# EagleVersion1_PowerPatch.net
KiCad netlist of a schematic drawn in EAGLE
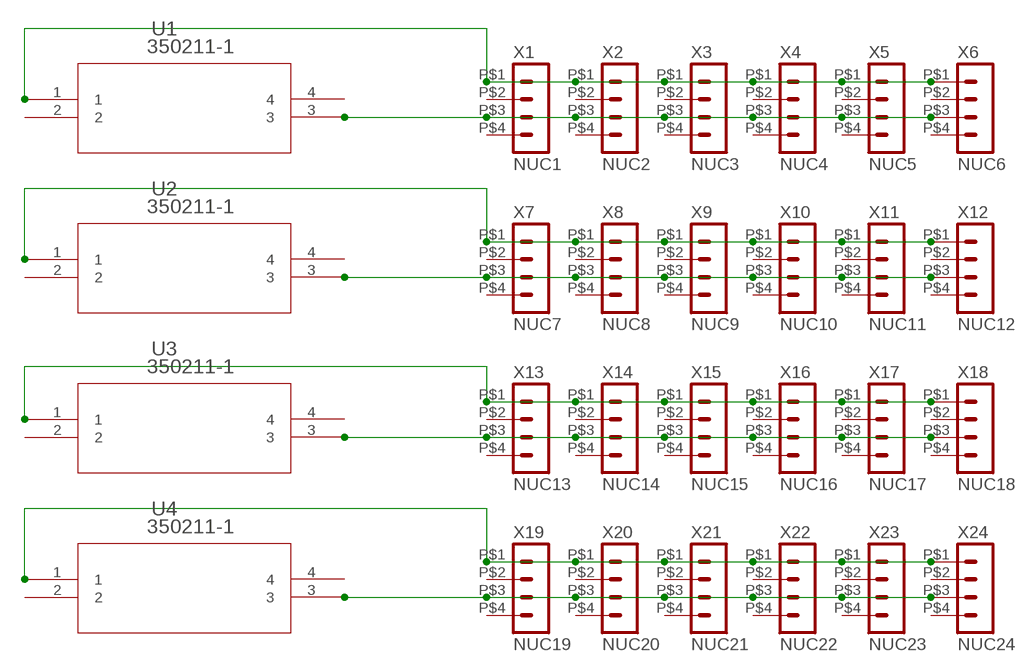
[diagram p0: schematic, sheet 1]

(export (version "E")
  (design (tool "Eeschema 10.0.6"))
  (components
    (comp (ref "U1")
      (value "350211-1")
      (footprint "eagle-import:350211-1")
      (fields
        (field (name "MANUFACTURER_PART_NUMBER") "3502111")
        (field (name "COPYRIGHT") "Copyright C 2015 Accelerated Designs. All rights reserved")
      )
      (libsource (lib "eagle-import") (part "350211-1"))
    )
    (comp (ref "U2")
      (value "350211-1")
      (footprint "eagle-import:350211-1")
      (fields
        (field (name "MANUFACTURER_PART_NUMBER") "3502111")
        (field (name "COPYRIGHT") "Copyright C 2015 Accelerated Designs. All rights reserved")
      )
      (libsource (lib "eagle-import") (part "350211-1"))
    )
    (comp (ref "U3")
      (value "350211-1")
      (footprint "eagle-import:350211-1")
      (fields
        (field (name "MANUFACTURER_PART_NUMBER") "3502111")
        (field (name "COPYRIGHT") "Copyright C 2015 Accelerated Designs. All rights reserved")
      )
      (libsource (lib "eagle-import") (part "350211-1"))
    )
    (comp (ref "U4")
      (value "350211-1")
      (footprint "eagle-import:350211-1")
      (fields
        (field (name "MANUFACTURER_PART_NUMBER") "3502111")
        (field (name "COPYRIGHT") "Copyright C 2015 Accelerated Designs. All rights reserved")
      )
      (libsource (lib "eagle-import") (part "350211-1"))
    )
    (comp (ref "X1")
      (value "NUC1")
      (footprint "eagle-import:43045-0412")
      (libsource (lib "eagle-import") (part "HEADER_POS4_?43045-0412"))
    )
    (comp (ref "X2")
      (value "NUC2")
      (footprint "eagle-import:43045-0412")
      (libsource (lib "eagle-import") (part "HEADER_POS4_?43045-0412"))
    )
    (comp (ref "X3")
      (value "NUC3")
      (footprint "eagle-import:43045-0412")
      (libsource (lib "eagle-import") (part "HEADER_POS4_?43045-0412"))
    )
    (comp (ref "X4")
      (value "NUC4")
      (footprint "eagle-import:43045-0412")
      (libsource (lib "eagle-import") (part "HEADER_POS4_?43045-0412"))
    )
    (comp (ref "X5")
      (value "NUC5")
      (footprint "eagle-import:43045-0412")
      (libsource (lib "eagle-import") (part "HEADER_POS4_?43045-0412"))
    )
    (comp (ref "X6")
      (value "NUC6")
      (footprint "eagle-import:43045-0412")
      (libsource (lib "eagle-import") (part "HEADER_POS4_?43045-0412"))
    )
    (comp (ref "X7")
      (value "NUC7")
      (footprint "eagle-import:43045-0412")
      (libsource (lib "eagle-import") (part "HEADER_POS4_?43045-0412"))
    )
    (comp (ref "X8")
      (value "NUC8")
      (footprint "eagle-import:43045-0412")
      (libsource (lib "eagle-import") (part "HEADER_POS4_?43045-0412"))
    )
    (comp (ref "X9")
      (value "NUC9")
      (footprint "eagle-import:43045-0412")
      (libsource (lib "eagle-import") (part "HEADER_POS4_?43045-0412"))
    )
    (comp (ref "X10")
      (value "NUC10")
      (footprint "eagle-import:43045-0412")
      (libsource (lib "eagle-import") (part "HEADER_POS4_?43045-0412"))
    )
    (comp (ref "X11")
      (value "NUC11")
      (footprint "eagle-import:43045-0412")
      (libsource (lib "eagle-import") (part "HEADER_POS4_?43045-0412"))
    )
    (comp (ref "X12")
      (value "NUC12")
      (footprint "eagle-import:43045-0412")
      (libsource (lib "eagle-import") (part "HEADER_POS4_?43045-0412"))
    )
    (comp (ref "X13")
      (value "NUC13")
      (footprint "eagle-import:43045-0412")
      (libsource (lib "eagle-import") (part "HEADER_POS4_?43045-0412"))
    )
    (comp (ref "X14")
      (value "NUC14")
      (footprint "eagle-import:43045-0412")
      (libsource (lib "eagle-import") (part "HEADER_POS4_?43045-0412"))
    )
    (comp (ref "X15")
      (value "NUC15")
      (footprint "eagle-import:43045-0412")
      (libsource (lib "eagle-import") (part "HEADER_POS4_?43045-0412"))
    )
    (comp (ref "X16")
      (value "NUC16")
      (footprint "eagle-import:43045-0412")
      (libsource (lib "eagle-import") (part "HEADER_POS4_?43045-0412"))
    )
    (comp (ref "X17")
      (value "NUC17")
      (footprint "eagle-import:43045-0412")
      (libsource (lib "eagle-import") (part "HEADER_POS4_?43045-0412"))
    )
    (comp (ref "X18")
      (value "NUC18")
      (footprint "eagle-import:43045-0412")
      (libsource (lib "eagle-import") (part "HEADER_POS4_?43045-0412"))
    )
    (comp (ref "X19")
      (value "NUC19")
      (footprint "eagle-import:43045-0412")
      (libsource (lib "eagle-import") (part "HEADER_POS4_?43045-0412"))
    )
    (comp (ref "X20")
      (value "NUC20")
      (footprint "eagle-import:43045-0412")
      (libsource (lib "eagle-import") (part "HEADER_POS4_?43045-0412"))
    )
    (comp (ref "X21")
      (value "NUC21")
      (footprint "eagle-import:43045-0412")
      (libsource (lib "eagle-import") (part "HEADER_POS4_?43045-0412"))
    )
    (comp (ref "X22")
      (value "NUC22")
      (footprint "eagle-import:43045-0412")
      (libsource (lib "eagle-import") (part "HEADER_POS4_?43045-0412"))
    )
    (comp (ref "X23")
      (value "NUC23")
      (footprint "eagle-import:43045-0412")
      (libsource (lib "eagle-import") (part "HEADER_POS4_?43045-0412"))
    )
    (comp (ref "X24")
      (value "NUC24")
      (footprint "eagle-import:43045-0412")
      (libsource (lib "eagle-import") (part "HEADER_POS4_?43045-0412"))
    )
  )
  (nets
    (net (code "1") (name "Net-(X1-1)") (class "Default")
      (node (ref "U1") (pin "1") (pinfunction "1_1") (pintype "passive"))
      (node (ref "X1") (pin "P$1") (pinfunction "1_P$1") (pintype "passive"))
      (node (ref "X2") (pin "P$1") (pinfunction "1_P$1") (pintype "passive"))
      (node (ref "X3") (pin "P$1") (pinfunction "1_P$1") (pintype "passive"))
      (node (ref "X4") (pin "P$1") (pinfunction "1_P$1") (pintype "passive"))
      (node (ref "X5") (pin "P$1") (pinfunction "1_P$1") (pintype "passive"))
      (node (ref "X6") (pin "P$1") (pinfunction "1_P$1") (pintype "passive"))
    )
    (net (code "2") (name "Net-(X1-3)") (class "Default")
      (node (ref "U1") (pin "3") (pinfunction "3_3") (pintype "passive"))
      (node (ref "X1") (pin "P$3") (pinfunction "3_P$3") (pintype "passive"))
      (node (ref "X2") (pin "P$3") (pinfunction "3_P$3") (pintype "passive"))
      (node (ref "X3") (pin "P$3") (pinfunction "3_P$3") (pintype "passive"))
      (node (ref "X4") (pin "P$3") (pinfunction "3_P$3") (pintype "passive"))
      (node (ref "X5") (pin "P$3") (pinfunction "3_P$3") (pintype "passive"))
      (node (ref "X6") (pin "P$3") (pinfunction "3_P$3") (pintype "passive"))
    )
    (net (code "3") (name "Net-(X10-1)") (class "Default")
      (node (ref "U2") (pin "1") (pinfunction "1_1") (pintype "passive"))
      (node (ref "X10") (pin "P$1") (pinfunction "1_P$1") (pintype "passive"))
      (node (ref "X11") (pin "P$1") (pinfunction "1_P$1") (pintype "passive"))
      (node (ref "X12") (pin "P$1") (pinfunction "1_P$1") (pintype "passive"))
      (node (ref "X7") (pin "P$1") (pinfunction "1_P$1") (pintype "passive"))
      (node (ref "X8") (pin "P$1") (pinfunction "1_P$1") (pintype "passive"))
      (node (ref "X9") (pin "P$1") (pinfunction "1_P$1") (pintype "passive"))
    )
    (net (code "4") (name "Net-(X10-3)") (class "Default")
      (node (ref "U2") (pin "3") (pinfunction "3_3") (pintype "passive"))
      (node (ref "X10") (pin "P$3") (pinfunction "3_P$3") (pintype "passive"))
      (node (ref "X11") (pin "P$3") (pinfunction "3_P$3") (pintype "passive"))
      (node (ref "X12") (pin "P$3") (pinfunction "3_P$3") (pintype "passive"))
      (node (ref "X7") (pin "P$3") (pinfunction "3_P$3") (pintype "passive"))
      (node (ref "X8") (pin "P$3") (pinfunction "3_P$3") (pintype "passive"))
      (node (ref "X9") (pin "P$3") (pinfunction "3_P$3") (pintype "passive"))
    )
    (net (code "5") (name "Net-(X13-1)") (class "Default")
      (node (ref "U3") (pin "1") (pinfunction "1_1") (pintype "passive"))
      (node (ref "X13") (pin "P$1") (pinfunction "1_P$1") (pintype "passive"))
      (node (ref "X14") (pin "P$1") (pinfunction "1_P$1") (pintype "passive"))
      (node (ref "X15") (pin "P$1") (pinfunction "1_P$1") (pintype "passive"))
      (node (ref "X16") (pin "P$1") (pinfunction "1_P$1") (pintype "passive"))
      (node (ref "X17") (pin "P$1") (pinfunction "1_P$1") (pintype "passive"))
      (node (ref "X18") (pin "P$1") (pinfunction "1_P$1") (pintype "passive"))
    )
    (net (code "6") (name "Net-(X13-3)") (class "Default")
      (node (ref "U3") (pin "3") (pinfunction "3_3") (pintype "passive"))
      (node (ref "X13") (pin "P$3") (pinfunction "3_P$3") (pintype "passive"))
      (node (ref "X14") (pin "P$3") (pinfunction "3_P$3") (pintype "passive"))
      (node (ref "X15") (pin "P$3") (pinfunction "3_P$3") (pintype "passive"))
      (node (ref "X16") (pin "P$3") (pinfunction "3_P$3") (pintype "passive"))
      (node (ref "X17") (pin "P$3") (pinfunction "3_P$3") (pintype "passive"))
      (node (ref "X18") (pin "P$3") (pinfunction "3_P$3") (pintype "passive"))
    )
    (net (code "7") (name "Net-(X19-1)") (class "Default")
      (node (ref "U4") (pin "1") (pinfunction "1_1") (pintype "passive"))
      (node (ref "X19") (pin "P$1") (pinfunction "1_P$1") (pintype "passive"))
      (node (ref "X20") (pin "P$1") (pinfunction "1_P$1") (pintype "passive"))
      (node (ref "X21") (pin "P$1") (pinfunction "1_P$1") (pintype "passive"))
      (node (ref "X22") (pin "P$1") (pinfunction "1_P$1") (pintype "passive"))
      (node (ref "X23") (pin "P$1") (pinfunction "1_P$1") (pintype "passive"))
      (node (ref "X24") (pin "P$1") (pinfunction "1_P$1") (pintype "passive"))
    )
    (net (code "8") (name "Net-(X19-3)") (class "Default")
      (node (ref "U4") (pin "3") (pinfunction "3_3") (pintype "passive"))
      (node (ref "X19") (pin "P$3") (pinfunction "3_P$3") (pintype "passive"))
      (node (ref "X20") (pin "P$3") (pinfunction "3_P$3") (pintype "passive"))
      (node (ref "X21") (pin "P$3") (pinfunction "3_P$3") (pintype "passive"))
      (node (ref "X22") (pin "P$3") (pinfunction "3_P$3") (pintype "passive"))
      (node (ref "X23") (pin "P$3") (pinfunction "3_P$3") (pintype "passive"))
      (node (ref "X24") (pin "P$3") (pinfunction "3_P$3") (pintype "passive"))
    )
    (net (code "9") (name "unconnected-(U1-Pad2)") (class "Default")
      (node (ref "U1") (pin "2") (pinfunction "2_2") (pintype "passive"))
    )
    (net (code "10") (name "unconnected-(U1-Pad4)") (class "Default")
      (node (ref "U1") (pin "4") (pinfunction "4_4") (pintype "passive"))
    )
    (net (code "11") (name "unconnected-(U2-Pad2)") (class "Default")
      (node (ref "U2") (pin "2") (pinfunction "2_2") (pintype "passive"))
    )
    (net (code "12") (name "unconnected-(U2-Pad4)") (class "Default")
      (node (ref "U2") (pin "4") (pinfunction "4_4") (pintype "passive"))
    )
    (net (code "13") (name "unconnected-(U3-Pad2)") (class "Default")
      (node (ref "U3") (pin "2") (pinfunction "2_2") (pintype "passive"))
    )
    (net (code "14") (name "unconnected-(U3-Pad4)") (class "Default")
      (node (ref "U3") (pin "4") (pinfunction "4_4") (pintype "passive"))
    )
    (net (code "15") (name "unconnected-(U4-Pad2)") (class "Default")
      (node (ref "U4") (pin "2") (pinfunction "2_2") (pintype "passive"))
    )
    (net (code "16") (name "unconnected-(U4-Pad4)") (class "Default")
      (node (ref "U4") (pin "4") (pinfunction "4_4") (pintype "passive"))
    )
    (net (code "17") (name "unconnected-(X1-2-PadP$2)") (class "Default")
      (node (ref "X1") (pin "P$2") (pinfunction "2_P$2") (pintype "passive"))
    )
    (net (code "18") (name "unconnected-(X1-4-PadP$4)") (class "Default")
      (node (ref "X1") (pin "P$4") (pinfunction "4_P$4") (pintype "passive"))
    )
    (net (code "19") (name "unconnected-(X2-2-PadP$2)") (class "Default")
      (node (ref "X2") (pin "P$2") (pinfunction "2_P$2") (pintype "passive"))
    )
    (net (code "20") (name "unconnected-(X2-4-PadP$4)") (class "Default")
      (node (ref "X2") (pin "P$4") (pinfunction "4_P$4") (pintype "passive"))
    )
    (net (code "21") (name "unconnected-(X3-2-PadP$2)") (class "Default")
      (node (ref "X3") (pin "P$2") (pinfunction "2_P$2") (pintype "passive"))
    )
    (net (code "22") (name "unconnected-(X3-4-PadP$4)") (class "Default")
      (node (ref "X3") (pin "P$4") (pinfunction "4_P$4") (pintype "passive"))
    )
    (net (code "23") (name "unconnected-(X4-2-PadP$2)") (class "Default")
      (node (ref "X4") (pin "P$2") (pinfunction "2_P$2") (pintype "passive"))
    )
    (net (code "24") (name "unconnected-(X4-4-PadP$4)") (class "Default")
      (node (ref "X4") (pin "P$4") (pinfunction "4_P$4") (pintype "passive"))
    )
    (net (code "25") (name "unconnected-(X5-2-PadP$2)") (class "Default")
      (node (ref "X5") (pin "P$2") (pinfunction "2_P$2") (pintype "passive"))
    )
    (net (code "26") (name "unconnected-(X5-4-PadP$4)") (class "Default")
      (node (ref "X5") (pin "P$4") (pinfunction "4_P$4") (pintype "passive"))
    )
    (net (code "27") (name "unconnected-(X6-2-PadP$2)") (class "Default")
      (node (ref "X6") (pin "P$2") (pinfunction "2_P$2") (pintype "passive"))
    )
    (net (code "28") (name "unconnected-(X6-4-PadP$4)") (class "Default")
      (node (ref "X6") (pin "P$4") (pinfunction "4_P$4") (pintype "passive"))
    )
    (net (code "29") (name "unconnected-(X7-2-PadP$2)") (class "Default")
      (node (ref "X7") (pin "P$2") (pinfunction "2_P$2") (pintype "passive"))
    )
    (net (code "30") (name "unconnected-(X7-4-PadP$4)") (class "Default")
      (node (ref "X7") (pin "P$4") (pinfunction "4_P$4") (pintype "passive"))
    )
    (net (code "31") (name "unconnected-(X8-2-PadP$2)") (class "Default")
      (node (ref "X8") (pin "P$2") (pinfunction "2_P$2") (pintype "passive"))
    )
    (net (code "32") (name "unconnected-(X8-4-PadP$4)") (class "Default")
      (node (ref "X8") (pin "P$4") (pinfunction "4_P$4") (pintype "passive"))
    )
    (net (code "33") (name "unconnected-(X9-2-PadP$2)") (class "Default")
      (node (ref "X9") (pin "P$2") (pinfunction "2_P$2") (pintype "passive"))
    )
    (net (code "34") (name "unconnected-(X9-4-PadP$4)") (class "Default")
      (node (ref "X9") (pin "P$4") (pinfunction "4_P$4") (pintype "passive"))
    )
    (net (code "35") (name "unconnected-(X10-2-PadP$2)") (class "Default")
      (node (ref "X10") (pin "P$2") (pinfunction "2_P$2") (pintype "passive"))
    )
    (net (code "36") (name "unconnected-(X10-4-PadP$4)") (class "Default")
      (node (ref "X10") (pin "P$4") (pinfunction "4_P$4") (pintype "passive"))
    )
    (net (code "37") (name "unconnected-(X11-2-PadP$2)") (class "Default")
      (node (ref "X11") (pin "P$2") (pinfunction "2_P$2") (pintype "passive"))
    )
    (net (code "38") (name "unconnected-(X11-4-PadP$4)") (class "Default")
      (node (ref "X11") (pin "P$4") (pinfunction "4_P$4") (pintype "passive"))
    )
    (net (code "39") (name "unconnected-(X12-2-PadP$2)") (class "Default")
      (node (ref "X12") (pin "P$2") (pinfunction "2_P$2") (pintype "passive"))
    )
    (net (code "40") (name "unconnected-(X12-4-PadP$4)") (class "Default")
      (node (ref "X12") (pin "P$4") (pinfunction "4_P$4") (pintype "passive"))
    )
    (net (code "41") (name "unconnected-(X13-2-PadP$2)") (class "Default")
      (node (ref "X13") (pin "P$2") (pinfunction "2_P$2") (pintype "passive"))
    )
    (net (code "42") (name "unconnected-(X13-4-PadP$4)") (class "Default")
      (node (ref "X13") (pin "P$4") (pinfunction "4_P$4") (pintype "passive"))
    )
    (net (code "43") (name "unconnected-(X14-2-PadP$2)") (class "Default")
      (node (ref "X14") (pin "P$2") (pinfunction "2_P$2") (pintype "passive"))
    )
    (net (code "44") (name "unconnected-(X14-4-PadP$4)") (class "Default")
      (node (ref "X14") (pin "P$4") (pinfunction "4_P$4") (pintype "passive"))
    )
    (net (code "45") (name "unconnected-(X15-2-PadP$2)") (class "Default")
      (node (ref "X15") (pin "P$2") (pinfunction "2_P$2") (pintype "passive"))
    )
    (net (code "46") (name "unconnected-(X15-4-PadP$4)") (class "Default")
      (node (ref "X15") (pin "P$4") (pinfunction "4_P$4") (pintype "passive"))
    )
    (net (code "47") (name "unconnected-(X16-2-PadP$2)") (class "Default")
      (node (ref "X16") (pin "P$2") (pinfunction "2_P$2") (pintype "passive"))
    )
    (net (code "48") (name "unconnected-(X16-4-PadP$4)") (class "Default")
      (node (ref "X16") (pin "P$4") (pinfunction "4_P$4") (pintype "passive"))
    )
    (net (code "49") (name "unconnected-(X17-2-PadP$2)") (class "Default")
      (node (ref "X17") (pin "P$2") (pinfunction "2_P$2") (pintype "passive"))
    )
    (net (code "50") (name "unconnected-(X17-4-PadP$4)") (class "Default")
      (node (ref "X17") (pin "P$4") (pinfunction "4_P$4") (pintype "passive"))
    )
    (net (code "51") (name "unconnected-(X18-2-PadP$2)") (class "Default")
      (node (ref "X18") (pin "P$2") (pinfunction "2_P$2") (pintype "passive"))
    )
    (net (code "52") (name "unconnected-(X18-4-PadP$4)") (class "Default")
      (node (ref "X18") (pin "P$4") (pinfunction "4_P$4") (pintype "passive"))
    )
    (net (code "53") (name "unconnected-(X19-2-PadP$2)") (class "Default")
      (node (ref "X19") (pin "P$2") (pinfunction "2_P$2") (pintype "passive"))
    )
    (net (code "54") (name "unconnected-(X19-4-PadP$4)") (class "Default")
      (node (ref "X19") (pin "P$4") (pinfunction "4_P$4") (pintype "passive"))
    )
    (net (code "55") (name "unconnected-(X20-2-PadP$2)") (class "Default")
      (node (ref "X20") (pin "P$2") (pinfunction "2_P$2") (pintype "passive"))
    )
    (net (code "56") (name "unconnected-(X20-4-PadP$4)") (class "Default")
      (node (ref "X20") (pin "P$4") (pinfunction "4_P$4") (pintype "passive"))
    )
    (net (code "57") (name "unconnected-(X21-2-PadP$2)") (class "Default")
      (node (ref "X21") (pin "P$2") (pinfunction "2_P$2") (pintype "passive"))
    )
    (net (code "58") (name "unconnected-(X21-4-PadP$4)") (class "Default")
      (node (ref "X21") (pin "P$4") (pinfunction "4_P$4") (pintype "passive"))
    )
    (net (code "59") (name "unconnected-(X22-2-PadP$2)") (class "Default")
      (node (ref "X22") (pin "P$2") (pinfunction "2_P$2") (pintype "passive"))
    )
    (net (code "60") (name "unconnected-(X22-4-PadP$4)") (class "Default")
      (node (ref "X22") (pin "P$4") (pinfunction "4_P$4") (pintype "passive"))
    )
    (net (code "61") (name "unconnected-(X23-2-PadP$2)") (class "Default")
      (node (ref "X23") (pin "P$2") (pinfunction "2_P$2") (pintype "passive"))
    )
    (net (code "62") (name "unconnected-(X23-4-PadP$4)") (class "Default")
      (node (ref "X23") (pin "P$4") (pinfunction "4_P$4") (pintype "passive"))
    )
    (net (code "63") (name "unconnected-(X24-2-PadP$2)") (class "Default")
      (node (ref "X24") (pin "P$2") (pinfunction "2_P$2") (pintype "passive"))
    )
    (net (code "64") (name "unconnected-(X24-4-PadP$4)") (class "Default")
      (node (ref "X24") (pin "P$4") (pinfunction "4_P$4") (pintype "passive"))
    )
  )
)
